# SEC_PCB.net
KiCad netlist of a schematic drawn in EAGLE
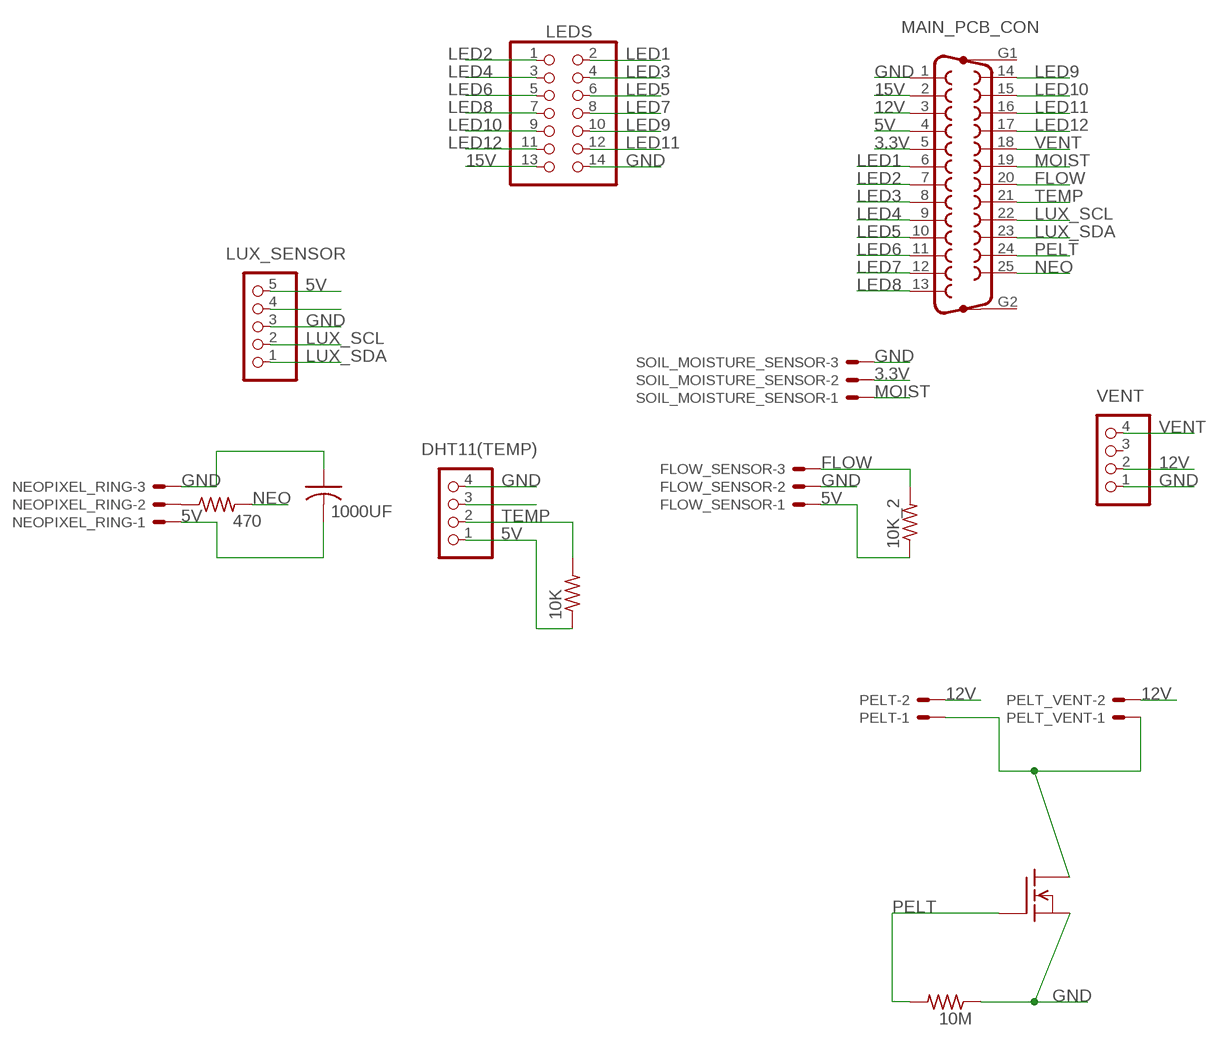
[diagram p0: schematic, sheet 1]

(export (version "E")
  (design (tool "Eeschema 10.0.6"))
  (components
    (comp (ref "10K")
      (value "FLIPFLOP-RES")
      (footprint "eagle-import:0805-THM")
      (libsource (lib "eagle-import") (part "FLIPFLOP-RES"))
    )
    (comp (ref "10K_2")
      (value "FLIPFLOP-RES")
      (footprint "eagle-import:0805-THM")
      (libsource (lib "eagle-import") (part "FLIPFLOP-RES"))
    )
    (comp (ref "10M")
      (value "FLIPFLOP-RES")
      (footprint "eagle-import:0805-THM")
      (libsource (lib "eagle-import") (part "FLIPFLOP-RES"))
    )
    (comp (ref "470")
      (value "FLIPFLOP-RES")
      (footprint "eagle-import:0805-THM")
      (libsource (lib "eagle-import") (part "FLIPFLOP-RES"))
    )
    (comp (ref "1000UF")
      (value "C-US050-035X075")
      (footprint "eagle-import:C050-035X075")
      (libsource (lib "eagle-import") (part "C-US050-035X075"))
    )
    (comp (ref "DHT11(TEMP)")
      (value "PINHD-1X4")
      (footprint "eagle-import:1X04")
      (libsource (lib "eagle-import") (part "PINHD-1X4"))
    )
    (comp (ref "FLOW_SENSOR")
      (value "JST-XH-03-PIN-LONG-PAD")
      (footprint "eagle-import:JST-XH-03-PACKAGE-LONG-PAD")
      (libsource (lib "eagle-import") (part "JST-XH-03-PIN-LONG-PAD"))
    )
    (comp (ref "LEDS")
      (value "PINHD-2X7")
      (footprint "eagle-import:2X07")
      (libsource (lib "eagle-import") (part "PINHD-2X7"))
    )
    (comp (ref "LUX_SENSOR")
      (value "PINHD-1X5")
      (footprint "eagle-import:1X05")
      (libsource (lib "eagle-import") (part "PINHD-1X5"))
    )
    (comp (ref "MAIN_PCB_CON")
      (value "F25VP")
      (footprint "eagle-import:F25VP")
      (libsource (lib "eagle-import") (part "F25VP"))
    )
    (comp (ref "NEOPIXEL_RING")
      (value "JST-XH-03-PIN-LONG-PAD")
      (footprint "eagle-import:JST-XH-03-PACKAGE-LONG-PAD")
      (libsource (lib "eagle-import") (part "JST-XH-03-PIN-LONG-PAD"))
    )
    (comp (ref "PELT")
      (value "JST-XH-02-PIN-LONG-PAD")
      (footprint "eagle-import:JST-XH-02-PACKAGE-LONG-PAD")
      (libsource (lib "eagle-import") (part "JST-XH-02-PIN-LONG-PAD"))
    )
    (comp (ref "PELT_TRANSISTOR")
      (value "FQN1N50C")
      (footprint "eagle-import:TO92")
      (libsource (lib "eagle-import") (part "FQN1N50C"))
    )
    (comp (ref "PELT_VENT")
      (value "JST-XH-02-PIN-LONG-PAD")
      (footprint "eagle-import:JST-XH-02-PACKAGE-LONG-PAD")
      (libsource (lib "eagle-import") (part "JST-XH-02-PIN-LONG-PAD"))
    )
    (comp (ref "SOIL_MOISTURE_SENSOR")
      (value "JST-XH-03-PIN-LONG-PAD")
      (footprint "eagle-import:JST-XH-03-PACKAGE-LONG-PAD")
      (libsource (lib "eagle-import") (part "JST-XH-03-PIN-LONG-PAD"))
    )
    (comp (ref "VENT")
      (value "PINHD-1X4")
      (footprint "eagle-import:1X04")
      (libsource (lib "eagle-import") (part "PINHD-1X4"))
    )
  )
  (nets
    (net (code "1") (name "/3.3V") (class "Default")
      (node (ref "MAIN_PCB_CON") (pin "5") (pinfunction "5_5") (pintype "passive"))
      (node (ref "SOIL_MOISTURE_SENSOR") (pin "2") (pinfunction "S_2") (pintype "passive"))
    )
    (net (code "2") (name "/5V") (class "Default")
      (node (ref "1000UF") (pin "2") (pinfunction "2_2") (pintype "passive"))
      (node (ref "10K") (pin "1") (pinfunction "1_1") (pintype "passive"))
      (node (ref "10K_2") (pin "1") (pinfunction "1_1") (pintype "passive"))
      (node (ref "DHT11(TEMP)") (pin "1") (pinfunction "1_1") (pintype "passive"))
      (node (ref "FLOW_SENSOR") (pin "1") (pinfunction "S_1") (pintype "passive"))
      (node (ref "LUX_SENSOR") (pin "5") (pinfunction "5_5") (pintype "passive"))
      (node (ref "MAIN_PCB_CON") (pin "4") (pinfunction "4_4") (pintype "passive"))
      (node (ref "NEOPIXEL_RING") (pin "1") (pinfunction "S_1") (pintype "passive"))
    )
    (net (code "3") (name "/12V") (class "Default")
      (node (ref "MAIN_PCB_CON") (pin "3") (pinfunction "3_3") (pintype "passive"))
      (node (ref "PELT") (pin "2") (pinfunction "S_2") (pintype "passive"))
      (node (ref "PELT_VENT") (pin "2") (pinfunction "S_2") (pintype "passive"))
      (node (ref "VENT") (pin "2") (pinfunction "2_2") (pintype "passive"))
    )
    (net (code "4") (name "/15V") (class "Default")
      (node (ref "LEDS") (pin "13") (pinfunction "13_13") (pintype "passive"))
      (node (ref "MAIN_PCB_CON") (pin "2") (pinfunction "2_2") (pintype "passive"))
    )
    (net (code "5") (name "/FLOW") (class "Default")
      (node (ref "10K_2") (pin "2") (pinfunction "2_2") (pintype "passive"))
      (node (ref "FLOW_SENSOR") (pin "3") (pinfunction "S_3") (pintype "passive"))
      (node (ref "MAIN_PCB_CON") (pin "20") (pinfunction "20_20") (pintype "passive"))
    )
    (net (code "6") (name "/GND") (class "Default")
      (node (ref "1000UF") (pin "1") (pinfunction "1_1") (pintype "passive"))
      (node (ref "10M") (pin "1") (pinfunction "1_1") (pintype "passive"))
      (node (ref "DHT11(TEMP)") (pin "4") (pinfunction "4_4") (pintype "passive"))
      (node (ref "FLOW_SENSOR") (pin "2") (pinfunction "S_2") (pintype "passive"))
      (node (ref "LEDS") (pin "14") (pinfunction "14_14") (pintype "passive"))
      (node (ref "LUX_SENSOR") (pin "3") (pinfunction "3_3") (pintype "passive"))
      (node (ref "MAIN_PCB_CON") (pin "1") (pinfunction "1_1") (pintype "passive"))
      (node (ref "NEOPIXEL_RING") (pin "3") (pinfunction "S_3") (pintype "passive"))
      (node (ref "PELT_TRANSISTOR") (pin "3") (pinfunction "S_3") (pintype "passive"))
      (node (ref "SOIL_MOISTURE_SENSOR") (pin "3") (pinfunction "S_3") (pintype "passive"))
      (node (ref "VENT") (pin "1") (pinfunction "1_1") (pintype "passive"))
    )
    (net (code "7") (name "/LED1") (class "Default")
      (node (ref "LEDS") (pin "2") (pinfunction "2_2") (pintype "passive"))
      (node (ref "MAIN_PCB_CON") (pin "6") (pinfunction "6_6") (pintype "passive"))
    )
    (net (code "8") (name "/LED2") (class "Default")
      (node (ref "LEDS") (pin "1") (pinfunction "1_1") (pintype "passive"))
      (node (ref "MAIN_PCB_CON") (pin "7") (pinfunction "7_7") (pintype "passive"))
    )
    (net (code "9") (name "/LED3") (class "Default")
      (node (ref "LEDS") (pin "4") (pinfunction "4_4") (pintype "passive"))
      (node (ref "MAIN_PCB_CON") (pin "8") (pinfunction "8_8") (pintype "passive"))
    )
    (net (code "10") (name "/LED4") (class "Default")
      (node (ref "LEDS") (pin "3") (pinfunction "3_3") (pintype "passive"))
      (node (ref "MAIN_PCB_CON") (pin "9") (pinfunction "9_9") (pintype "passive"))
    )
    (net (code "11") (name "/LED5") (class "Default")
      (node (ref "LEDS") (pin "6") (pinfunction "6_6") (pintype "passive"))
      (node (ref "MAIN_PCB_CON") (pin "10") (pinfunction "10_10") (pintype "passive"))
    )
    (net (code "12") (name "/LED6") (class "Default")
      (node (ref "LEDS") (pin "5") (pinfunction "5_5") (pintype "passive"))
      (node (ref "MAIN_PCB_CON") (pin "11") (pinfunction "11_11") (pintype "passive"))
    )
    (net (code "13") (name "/LED7") (class "Default")
      (node (ref "LEDS") (pin "8") (pinfunction "8_8") (pintype "passive"))
      (node (ref "MAIN_PCB_CON") (pin "12") (pinfunction "12_12") (pintype "passive"))
    )
    (net (code "14") (name "/LED8") (class "Default")
      (node (ref "LEDS") (pin "7") (pinfunction "7_7") (pintype "passive"))
      (node (ref "MAIN_PCB_CON") (pin "13") (pinfunction "13_13") (pintype "passive"))
    )
    (net (code "15") (name "/LED9") (class "Default")
      (node (ref "LEDS") (pin "10") (pinfunction "10_10") (pintype "passive"))
      (node (ref "MAIN_PCB_CON") (pin "14") (pinfunction "14_14") (pintype "passive"))
    )
    (net (code "16") (name "/LED10") (class "Default")
      (node (ref "LEDS") (pin "9") (pinfunction "9_9") (pintype "passive"))
      (node (ref "MAIN_PCB_CON") (pin "15") (pinfunction "15_15") (pintype "passive"))
    )
    (net (code "17") (name "/LED11") (class "Default")
      (node (ref "LEDS") (pin "12") (pinfunction "12_12") (pintype "passive"))
      (node (ref "MAIN_PCB_CON") (pin "16") (pinfunction "16_16") (pintype "passive"))
    )
    (net (code "18") (name "/LED12") (class "Default")
      (node (ref "LEDS") (pin "11") (pinfunction "11_11") (pintype "passive"))
      (node (ref "MAIN_PCB_CON") (pin "17") (pinfunction "17_17") (pintype "passive"))
    )
    (net (code "19") (name "/LUX_SCL") (class "Default")
      (node (ref "LUX_SENSOR") (pin "2") (pinfunction "2_2") (pintype "passive"))
      (node (ref "MAIN_PCB_CON") (pin "22") (pinfunction "22_22") (pintype "passive"))
    )
    (net (code "20") (name "/LUX_SDA") (class "Default")
      (node (ref "LUX_SENSOR") (pin "1") (pinfunction "1_1") (pintype "passive"))
      (node (ref "MAIN_PCB_CON") (pin "23") (pinfunction "23_23") (pintype "passive"))
    )
    (net (code "21") (name "/MOIST") (class "Default")
      (node (ref "MAIN_PCB_CON") (pin "19") (pinfunction "19_19") (pintype "passive"))
      (node (ref "SOIL_MOISTURE_SENSOR") (pin "1") (pinfunction "S_1") (pintype "passive"))
    )
    (net (code "22") (name "/NEO") (class "Default")
      (node (ref "470") (pin "2") (pinfunction "2_2") (pintype "passive"))
      (node (ref "MAIN_PCB_CON") (pin "25") (pinfunction "25_25") (pintype "passive"))
    )
    (net (code "23") (name "/PELT") (class "Default")
      (node (ref "10M") (pin "2") (pinfunction "2_2") (pintype "passive"))
      (node (ref "MAIN_PCB_CON") (pin "24") (pinfunction "24_24") (pintype "passive"))
      (node (ref "PELT_TRANSISTOR") (pin "1") (pinfunction "G_1") (pintype "passive"))
    )
    (net (code "24") (name "/TEMP") (class "Default")
      (node (ref "10K") (pin "2") (pinfunction "2_2") (pintype "passive"))
      (node (ref "DHT11(TEMP)") (pin "2") (pinfunction "2_2") (pintype "passive"))
      (node (ref "MAIN_PCB_CON") (pin "21") (pinfunction "21_21") (pintype "passive"))
    )
    (net (code "25") (name "/VENT") (class "Default")
      (node (ref "MAIN_PCB_CON") (pin "18") (pinfunction "18_18") (pintype "passive"))
      (node (ref "VENT") (pin "4") (pinfunction "4_4") (pintype "passive"))
    )
    (net (code "26") (name "Net-(NEOPIXEL_RINGB-S)") (class "Default")
      (node (ref "470") (pin "1") (pinfunction "1_1") (pintype "passive"))
      (node (ref "NEOPIXEL_RING") (pin "2") (pinfunction "S_2") (pintype "passive"))
    )
    (net (code "27") (name "Net-(PELTA-S)") (class "Default")
      (node (ref "PELT") (pin "1") (pinfunction "S_1") (pintype "passive"))
      (node (ref "PELT_TRANSISTOR") (pin "2") (pinfunction "D_2") (pintype "passive"))
      (node (ref "PELT_VENT") (pin "1") (pinfunction "S_1") (pintype "passive"))
    )
    (net (code "28") (name "unconnected-(DHT11(TEMP)-Pad3)") (class "Default")
      (node (ref "DHT11(TEMP)") (pin "3") (pinfunction "3_3") (pintype "passive"))
    )
    (net (code "29") (name "unconnected-(LUX_SENSOR-Pad4)") (class "Default")
      (node (ref "LUX_SENSOR") (pin "4") (pinfunction "4_4") (pintype "passive"))
    )
    (net (code "30") (name "unconnected-(MAIN_PCB_CON-PadG1)") (class "Default")
      (node (ref "MAIN_PCB_CON") (pin "G1") (pinfunction "G1_G1") (pintype "passive"))
    )
    (net (code "31") (name "unconnected-(MAIN_PCB_CON-PadG2)") (class "Default")
      (node (ref "MAIN_PCB_CON") (pin "G2") (pinfunction "G2_G2") (pintype "passive"))
    )
    (net (code "32") (name "unconnected-(VENT-Pad3)") (class "Default")
      (node (ref "VENT") (pin "3") (pinfunction "3_3") (pintype "passive"))
    )
  )
)
